# ESP32-RFID_IoT.net
KiCad netlist of a schematic drawn in EAGLE
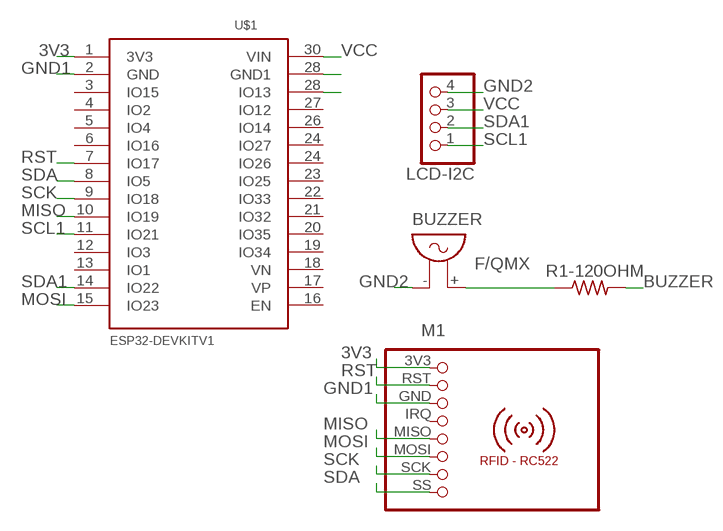
[diagram p0: schematic, sheet 1]

(export (version "E")
  (design (tool "Eeschema 10.0.6"))
  (components
    (comp (ref "BUZZER")
      (value "F/QMX")
      (footprint "eagle-import:F_QMX")
      (libsource (lib "eagle-import") (part "F/QMX"))
    )
    (comp (ref "LCD-I2C")
      (value "PINHD-1X4")
      (footprint "eagle-import:1X04")
      (libsource (lib "eagle-import") (part "PINHD-1X4"))
    )
    (comp (ref "M1")
      (value "RFID-RC522")
      (footprint "eagle-import:RFID-RC522")
      (libsource (lib "eagle-import") (part "RFID-RC522"))
    )
    (comp (ref "R1-120OHM")
      (value "R-US_0204/7")
      (footprint "eagle-import:0204_7")
      (libsource (lib "eagle-import") (part "R-US_0204/7"))
    )
    (comp (ref "U$1")
      (value "ESP32DEVKITV1")
      (footprint "eagle-import:ESP32-DEVKITV1")
      (libsource (lib "eagle-import") (part "ESP32DEVKITV1"))
    )
  )
  (nets
    (net (code "1") (name "/3V3") (class "Default")
      (node (ref "M1") (pin "3V3") (pinfunction "1_3V3") (pintype "passive"))
      (node (ref "U$1") (pin "1") (pinfunction "3V3_1") (pintype "bidirectional"))
    )
    (net (code "2") (name "/BUZZER") (class "Default")
      (node (ref "R1-120OHM") (pin "2") (pinfunction "2_2") (pintype "passive"))
      (node (ref "U$1") (pin "28") (pinfunction "IO13_28") (pintype "bidirectional"))
    )
    (net (code "3") (name "/GND1") (class "Default")
      (node (ref "M1") (pin "GND") (pinfunction "3_GND") (pintype "passive"))
      (node (ref "U$1") (pin "2") (pinfunction "GND_2") (pintype "bidirectional"))
    )
    (net (code "4") (name "/GND2") (class "Default")
      (node (ref "BUZZER") (pin "-") (pinfunction "1_-") (pintype "passive"))
      (node (ref "LCD-I2C") (pin "4") (pinfunction "4_4") (pintype "passive"))
      (node (ref "U$1") (pin "28") (pinfunction "GND1_28") (pintype "bidirectional"))
    )
    (net (code "5") (name "/MISO") (class "Default")
      (node (ref "M1") (pin "MISO") (pinfunction "5_MISO") (pintype "passive"))
      (node (ref "U$1") (pin "10") (pinfunction "IO19_10") (pintype "bidirectional"))
    )
    (net (code "6") (name "/MOSI") (class "Default")
      (node (ref "M1") (pin "MOSI") (pinfunction "6_MOSI") (pintype "passive"))
      (node (ref "U$1") (pin "15") (pinfunction "IO23_15") (pintype "bidirectional"))
    )
    (net (code "7") (name "/RST") (class "Default")
      (node (ref "M1") (pin "RST") (pinfunction "2_RST") (pintype "passive"))
      (node (ref "U$1") (pin "7") (pinfunction "IO17_7") (pintype "bidirectional"))
    )
    (net (code "8") (name "/SCK") (class "Default")
      (node (ref "M1") (pin "SCK") (pinfunction "7_SCK") (pintype "passive"))
      (node (ref "U$1") (pin "9") (pinfunction "IO18_9") (pintype "bidirectional"))
    )
    (net (code "9") (name "/SCL1") (class "Default")
      (node (ref "LCD-I2C") (pin "1") (pinfunction "1_1") (pintype "passive"))
      (node (ref "U$1") (pin "11") (pinfunction "IO21_11") (pintype "bidirectional"))
    )
    (net (code "10") (name "/SDA") (class "Default")
      (node (ref "M1") (pin "SS") (pinfunction "8_SS") (pintype "passive"))
      (node (ref "U$1") (pin "8") (pinfunction "IO5_8") (pintype "bidirectional"))
    )
    (net (code "11") (name "/SDA1") (class "Default")
      (node (ref "LCD-I2C") (pin "2") (pinfunction "2_2") (pintype "passive"))
      (node (ref "U$1") (pin "14") (pinfunction "IO22_14") (pintype "bidirectional"))
    )
    (net (code "12") (name "/VCC") (class "Default")
      (node (ref "LCD-I2C") (pin "3") (pinfunction "3_3") (pintype "passive"))
      (node (ref "U$1") (pin "30") (pinfunction "VIN_30") (pintype "bidirectional"))
    )
    (net (code "13") (name "Net-(BUZZER-2)") (class "Default")
      (node (ref "BUZZER") (pin "+") (pinfunction "2_+") (pintype "passive"))
      (node (ref "R1-120OHM") (pin "1") (pinfunction "1_1") (pintype "passive"))
    )
    (net (code "14") (name "unconnected-(M1-4-PadIRQ)") (class "Default")
      (node (ref "M1") (pin "IRQ") (pinfunction "4_IRQ") (pintype "passive"))
    )
    (net (code "15") (name "unconnected-(U$1-EN-Pad16)") (class "Default")
      (node (ref "U$1") (pin "16") (pinfunction "EN_16") (pintype "bidirectional"))
    )
    (net (code "16") (name "unconnected-(U$1-IO1-Pad13)") (class "Default")
      (node (ref "U$1") (pin "13") (pinfunction "IO1_13") (pintype "bidirectional"))
    )
    (net (code "17") (name "unconnected-(U$1-IO2-Pad4)") (class "Default")
      (node (ref "U$1") (pin "4") (pinfunction "IO2_4") (pintype "bidirectional"))
    )
    (net (code "18") (name "unconnected-(U$1-IO3-Pad12)") (class "Default")
      (node (ref "U$1") (pin "12") (pinfunction "IO3_12") (pintype "bidirectional"))
    )
    (net (code "19") (name "unconnected-(U$1-IO4-Pad5)") (class "Default")
      (node (ref "U$1") (pin "5") (pinfunction "IO4_5") (pintype "bidirectional"))
    )
    (net (code "20") (name "unconnected-(U$1-IO12-Pad27)") (class "Default")
      (node (ref "U$1") (pin "27") (pinfunction "IO12_27") (pintype "bidirectional"))
    )
    (net (code "21") (name "unconnected-(U$1-IO14-Pad26)") (class "Default")
      (node (ref "U$1") (pin "26") (pinfunction "IO14_26") (pintype "bidirectional"))
    )
    (net (code "22") (name "unconnected-(U$1-IO15-Pad3)") (class "Default")
      (node (ref "U$1") (pin "3") (pinfunction "IO15_3") (pintype "bidirectional"))
    )
    (net (code "23") (name "unconnected-(U$1-IO16-Pad6)") (class "Default")
      (node (ref "U$1") (pin "6") (pinfunction "IO16_6") (pintype "bidirectional"))
    )
    (net (code "24") (name "unconnected-(U$1-IO25-Pad23)") (class "Default")
      (node (ref "U$1") (pin "23") (pinfunction "IO25_23") (pintype "bidirectional"))
    )
    (net (code "25") (name "unconnected-(U$1-IO26-Pad24)") (class "Default")
      (node (ref "U$1") (pin "24") (pinfunction "IO26_24") (pintype "bidirectional"))
    )
    (net (code "26") (name "unconnected-(U$1-IO27-Pad24)") (class "Default")
      (node (ref "U$1") (pin "24") (pinfunction "IO27_24") (pintype "bidirectional"))
    )
    (net (code "27") (name "unconnected-(U$1-IO32-Pad21)") (class "Default")
      (node (ref "U$1") (pin "21") (pinfunction "IO32_21") (pintype "bidirectional"))
    )
    (net (code "28") (name "unconnected-(U$1-IO33-Pad22)") (class "Default")
      (node (ref "U$1") (pin "22") (pinfunction "IO33_22") (pintype "bidirectional"))
    )
    (net (code "29") (name "unconnected-(U$1-IO34-Pad19)") (class "Default")
      (node (ref "U$1") (pin "19") (pinfunction "IO34_19") (pintype "bidirectional"))
    )
    (net (code "30") (name "unconnected-(U$1-IO35-Pad20)") (class "Default")
      (node (ref "U$1") (pin "20") (pinfunction "IO35_20") (pintype "bidirectional"))
    )
    (net (code "31") (name "unconnected-(U$1-VN-Pad18)") (class "Default")
      (node (ref "U$1") (pin "18") (pinfunction "VN_18") (pintype "bidirectional"))
    )
    (net (code "32") (name "unconnected-(U$1-VP-Pad17)") (class "Default")
      (node (ref "U$1") (pin "17") (pinfunction "VP_17") (pintype "bidirectional"))
    )
  )
)
